# PROC099B_XDS110_Interface_1A.net
KiCad netlist of a schematic drawn in Altium Designer
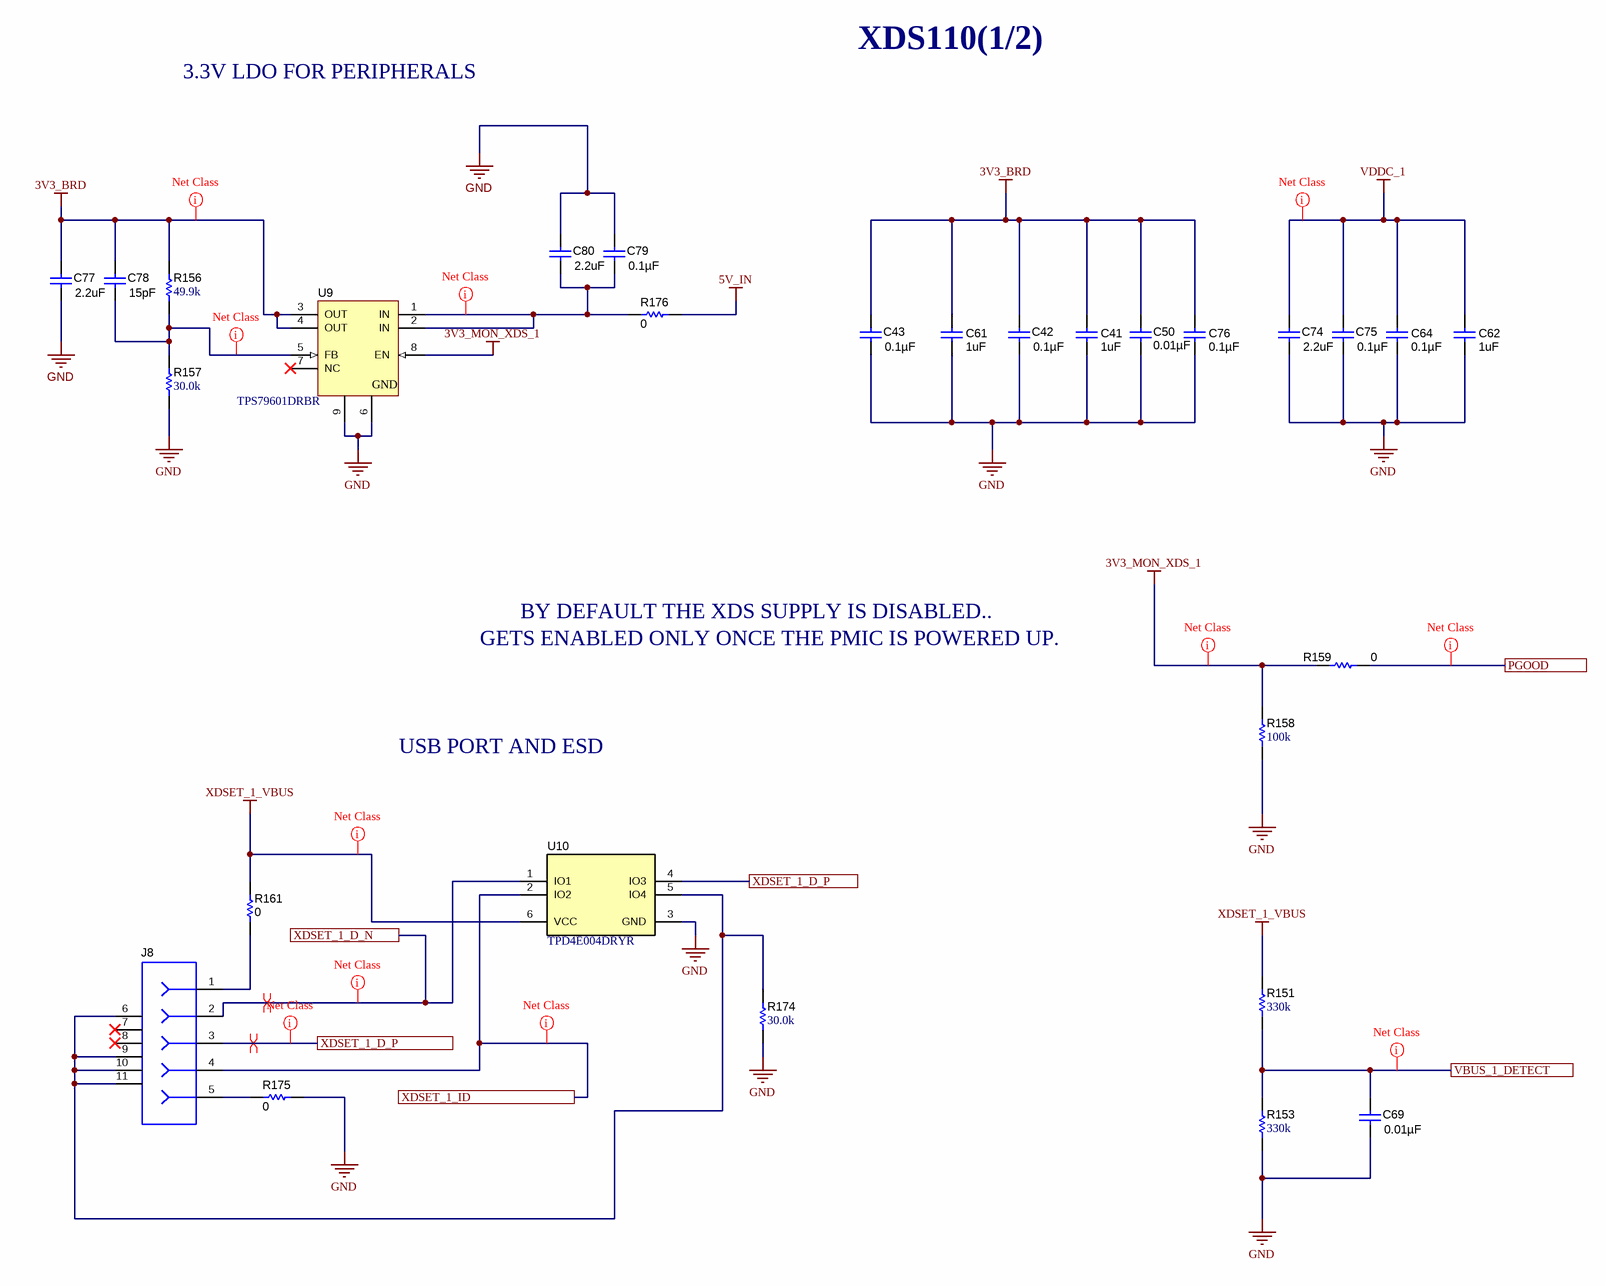
[diagram p0: PROC099B_XDS110 Interface_1A.SchDoc]

(export (version "E")
  (design (tool "Eeschema 10.0.6"))
  (components
    (comp (ref "C41")
      (value "GCM155C71A105KE38D")
      (footprint "0402_070")
      (description "CAP, CERM, 1 uF, 10 V, +/- 10%, X7S, AEC-Q200 Grade 1, 0402")
      (fields
        (field (name "MANUFACTURER") "MuRata")
        (field (name "VALUEDISPLAYED") "1uF")
        (field (name "PUBLISHER") "Texas Instruments")
      )
      (libsource (lib "Altium Vault - TI") (part "Capacitor"))
    )
    (comp (ref "C42")
      (value "C0402C104K8RACTU")
      (footprint "0402L")
      (description "CAP, CERM, 0.1 µF, 10 V,+/- 10%, X7R, 0402")
      (fields (field (name "MANUFACTURER") "Kemet") (field (name "VALUEDISPLAYED") "0.1µF"))
      (libsource (lib "Altium Vault - TI") (part "Capacitor"))
    )
    (comp (ref "C43")
      (value "C0402C104K8RACTU")
      (footprint "0402L")
      (description "CAP, CERM, 0.1 µF, 10 V,+/- 10%, X7R, 0402")
      (fields (field (name "MANUFACTURER") "Kemet") (field (name "VALUEDISPLAYED") "0.1µF"))
      (libsource (lib "Altium Vault - TI") (part "Capacitor"))
    )
    (comp (ref "C50")
      (value "C0402C103K4RACTU")
      (footprint "0402S")
      (description "CAP, CERM, 0.01 µF, 16 V,+/- 10%, X7R, 0402")
      (fields (field (name "MANUFACTURER") "Kemet") (field (name "VALUEDISPLAYED") "0.01µF"))
      (libsource (lib "Altium Vault - TI") (part "Capacitor"))
    )
    (comp (ref "C61")
      (value "GCM155C71A105KE38D")
      (footprint "0402_070")
      (description "CAP, CERM, 1 uF, 10 V, +/- 10%, X7S, AEC-Q200 Grade 1, 0402")
      (fields
        (field (name "MANUFACTURER") "MuRata")
        (field (name "VALUEDISPLAYED") "1uF")
        (field (name "PUBLISHER") "Texas Instruments")
      )
      (libsource (lib "Altium Vault - TI") (part "Capacitor"))
    )
    (comp (ref "C62")
      (value "GCM155C71A105KE38D")
      (footprint "0402_070")
      (description "CAP, CERM, 1 uF, 10 V, +/- 10%, X7S, AEC-Q200 Grade 1, 0402")
      (fields
        (field (name "MANUFACTURER") "MuRata")
        (field (name "VALUEDISPLAYED") "1uF")
        (field (name "PUBLISHER") "Texas Instruments")
      )
      (libsource (lib "Altium Vault - TI") (part "Capacitor"))
    )
    (comp (ref "C64")
      (value "C0402C104K8RACTU")
      (footprint "0402L")
      (description "CAP, CERM, 0.1 µF, 10 V,+/- 10%, X7R, 0402")
      (fields (field (name "MANUFACTURER") "Kemet") (field (name "VALUEDISPLAYED") "0.1µF"))
      (libsource (lib "Altium Vault - TI") (part "Capacitor"))
    )
    (comp (ref "C69")
      (value "C0402C103K4RACTU")
      (footprint "0402L")
      (description "CAP, CERM, 0.01 µF, 16 V,+/- 10%, X7R, 0402")
      (fields (field (name "MANUFACTURER") "Kemet") (field (name "VALUEDISPLAYED") "0.01µF"))
      (libsource (lib "Altium Vault - TI") (part "Capacitor"))
    )
    (comp (ref "C74")
      (value "C1005X7S1A225K050BC")
      (footprint "0402_065L")
      (description "CAP, CERM, 2.2 uF, 10 V, +/- 10%, X7S, 0402")
      (fields
        (field (name "MANUFACTURER") "TDK")
        (field (name "VALUEDISPLAYED") "2.2uF")
        (field (name "PUBLISHER") "Texas Instruments")
      )
      (libsource (lib "Altium Vault - TI") (part "CMP-0006302-2"))
    )
    (comp (ref "C75")
      (value "C0402C104K8RACTU")
      (footprint "0402L")
      (description "CAP, CERM, 0.1 µF, 10 V,+/- 10%, X7R, 0402")
      (fields (field (name "MANUFACTURER") "Kemet") (field (name "VALUEDISPLAYED") "0.1µF"))
      (libsource (lib "Altium Vault - TI") (part "Capacitor"))
    )
    (comp (ref "C76")
      (value "C0402C104K8RACTU")
      (footprint "0402L")
      (description "CAP, CERM, 0.1 µF, 10 V,+/- 10%, X7R, 0402")
      (fields (field (name "MANUFACTURER") "Kemet") (field (name "VALUEDISPLAYED") "0.1µF"))
      (libsource (lib "Altium Vault - TI") (part "Capacitor"))
    )
    (comp (ref "C77")
      (value "C1005X7S1A225K050BC")
      (footprint "0402_065L")
      (description "CAP, CERM, 2.2 uF, 10 V, +/- 10%, X7S, 0402")
      (fields
        (field (name "MANUFACTURER") "TDK")
        (field (name "VALUEDISPLAYED") "2.2uF")
        (field (name "PUBLISHER") "Texas Instruments")
      )
      (libsource (lib "Altium Vault - TI") (part "CMP-0006302-2"))
    )
    (comp (ref "C78")
      (value "04025A150FAT2A")
      (footprint "0402L")
      (description "CAP, CERM, 15 pF, 50 V,+/- 1%, C0G/NP0, 0402")
      (fields (field (name "MANUFACTURER") "AVX") (field (name "VALUEDISPLAYED") "15pF"))
      (libsource (lib "Altium Vault - TI") (part "Capacitor"))
    )
    (comp (ref "C79")
      (value "C0402C104K8RACTU")
      (footprint "0402L")
      (description "CAP, CERM, 0.1 µF, 10 V,+/- 10%, X7R, 0402")
      (fields (field (name "MANUFACTURER") "Kemet") (field (name "VALUEDISPLAYED") "0.1µF"))
      (libsource (lib "Altium Vault - TI") (part "Capacitor"))
    )
    (comp (ref "C80")
      (value "C1005X7S1A225K050BC")
      (footprint "0402_065L")
      (description "CAP, CERM, 2.2 uF, 10 V, +/- 10%, X7S, 0402")
      (fields
        (field (name "MANUFACTURER") "TDK")
        (field (name "VALUEDISPLAYED") "2.2uF")
        (field (name "PUBLISHER") "Texas Instruments")
      )
      (libsource (lib "Altium Vault - TI") (part "CMP-0006302-2"))
    )
    (comp (ref "J8")
      (value "105017-0001")
      (footprint "CONN_105017-0001")
      (description "Connector, Receptacle, Micro-USB Type B, R/A, Bottom Mount SMT")
      (fields (field (name "MANUFACTURER") "Molex") (field (name "PUBLISHER") "Texas Instruments"))
      (libsource (lib "Altium Vault - TI") (part "CONN_105017-0001"))
    )
    (comp (ref "R151")
      (value "CRCW0402330KFKED")
      (footprint "0402L")
      (description "RES, 330 k, 1%, 0.063 W, AEC-Q200 Grade 0, 0402")
      (fields (field (name "MANUFACTURER") "Vishay-Dale") (field (name "VALUEDISPLAYED") "330k"))
      (libsource (lib "Altium Vault - TI") (part "Resistor"))
    )
    (comp (ref "R153")
      (value "CRCW0402330KFKED")
      (footprint "0402L")
      (description "RES, 330 k, 1%, 0.063 W, AEC-Q200 Grade 0, 0402")
      (fields (field (name "MANUFACTURER") "Vishay-Dale") (field (name "VALUEDISPLAYED") "330k"))
      (libsource (lib "Altium Vault - TI") (part "Resistor"))
    )
    (comp (ref "R156")
      (value "CRCW040249K9FKED")
      (footprint "0402L")
      (description "RES, 49.9 k, 1%, 0.063 W, AEC-Q200 Grade 0, 0402")
      (fields (field (name "MANUFACTURER") "Vishay-Dale") (field (name "VALUEDISPLAYED") "49.9k"))
      (libsource (lib "Altium Vault - TI") (part "Resistor"))
    )
    (comp (ref "R157")
      (value "CRCW040230K0FKED")
      (footprint "0402L")
      (description "RES, 30.0 k, 1%, 0.063 W, AEC-Q200 Grade 0, 0402")
      (fields (field (name "MANUFACTURER") "Vishay-Dale") (field (name "VALUEDISPLAYED") "30.0k"))
      (libsource (lib "Altium Vault - TI") (part "Resistor"))
    )
    (comp (ref "R158")
      (value "CRCW0402100KFKED")
      (footprint "0402L")
      (description "RES, 100 k, 1%, 0.063 W, AEC-Q200 Grade 0, 0402")
      (fields (field (name "MANUFACTURER") "Vishay-Dale") (field (name "VALUEDISPLAYED") "100k"))
      (libsource (lib "Altium Vault - TI") (part "Resistor"))
    )
    (comp (ref "R159")
      (value "ERJ-2GE0R00X")
      (footprint "0402L")
      (description "RES, 0, 5%, 0.063 W, 0402")
      (fields
        (field (name "MANUFACTURER") "Panasonic")
        (field (name "VALUEDISPLAYED") "0")
        (field (name "PUBLISHER") "Texas Instruments")
      )
      (libsource (lib "Altium Vault - TI") (part "Resistor"))
    )
    (comp (ref "R161")
      (value "MCT06030Z0000ZP500")
      (footprint "0603")
      (description "RES, 0, 5%, 0.125 W, 0603")
      (fields
        (field (name "MANUFACTURER") "Vishay/Beyschlag")
        (field (name "VALUEDISPLAYED") "0")
        (field (name "PUBLISHER") "Texas Instruments")
      )
      (libsource (lib "Altium Vault - TI") (part "Resistor"))
    )
    (comp (ref "R174")
      (value "CRCW040230K0FKED")
      (footprint "0402L")
      (description "RES, 30.0 k, 1%, 0.063 W, AEC-Q200 Grade 0, 0402")
      (fields (field (name "MANUFACTURER") "Vishay-Dale") (field (name "VALUEDISPLAYED") "30.0k"))
      (libsource (lib "Altium Vault - TI") (part "Resistor"))
    )
    (comp (ref "R175")
      (value "MCT06030Z0000ZP500")
      (footprint "0603")
      (description "RES, 0, 5%, 0.125 W, 0603")
      (fields
        (field (name "MANUFACTURER") "Vishay/Beyschlag")
        (field (name "VALUEDISPLAYED") "0")
        (field (name "PUBLISHER") "Texas Instruments")
      )
      (libsource (lib "Altium Vault - TI") (part "Resistor"))
    )
    (comp (ref "R176")
      (value "MCT06030Z0000ZP500")
      (footprint "0603")
      (description "RES, 0, 5%, 0.125 W, 0603")
      (fields
        (field (name "MANUFACTURER") "Vishay/Beyschlag")
        (field (name "VALUEDISPLAYED") "0")
        (field (name "PUBLISHER") "Texas Instruments")
      )
      (libsource (lib "Altium Vault - TI") (part "Resistor"))
    )
    (comp (ref "U9")
      (value "TPS79601DRBR")
      (footprint "DRB0008B")
      (fields (field (name "MANUFACTURER") "Texas Instruments") (field (name "PARTNUMBER") "TPS79601DRBR"))
      (libsource (lib "Altium Vault - TI") (part "CMP-0036402-3"))
    )
    (comp (ref "U10")
      (value "TPD4E004DRYR")
      (footprint "DRY0006A")
      (fields (field (name "MANUFACTURER") "Texas Instruments") (field (name "PARTNUMBER") "TPD4E004DRYR"))
      (libsource (lib "Altium Vault - TI") (part "CMP-0043115-2"))
    )
  )
  (nets
    (net (code "1") (name "/PGOOD") (class "Default")
      (node (ref "R159") (pin "1") (pinfunction "1_1") (pintype "passive"))
    )
    (net (code "2") (name "/VBUS_1_DETECT") (class "Default")
      (node (ref "C69") (pin "2") (pinfunction "2_2") (pintype "passive"))
      (node (ref "R151") (pin "1") (pinfunction "1_1") (pintype "passive"))
      (node (ref "R153") (pin "2") (pinfunction "2_2") (pintype "passive"))
    )
    (net (code "3") (name "/XDSET_1_D_N") (class "Default")
      (node (ref "J8") (pin "2") (pintype "passive"))
      (node (ref "U10") (pin "1") (pinfunction "IO1_1") (pintype "passive"))
    )
    (net (code "4") (name "/XDSET_1_D_P") (class "Default")
      (node (ref "J8") (pin "3") (pintype "passive"))
      (node (ref "U10") (pin "4") (pinfunction "IO3_4") (pintype "passive"))
    )
    (net (code "5") (name "/XDSET_1_ID") (class "Default")
      (node (ref "J8") (pin "4") (pintype "passive"))
      (node (ref "U10") (pin "2") (pinfunction "IO2_2") (pintype "passive"))
    )
    (net (code "6") (name "3V3_BRD") (class "Default")
      (node (ref "C41") (pin "1") (pinfunction "1_1") (pintype "passive"))
      (node (ref "C42") (pin "2") (pinfunction "2_2") (pintype "passive"))
      (node (ref "C43") (pin "2") (pinfunction "2_2") (pintype "passive"))
      (node (ref "C50") (pin "1") (pinfunction "1_1") (pintype "passive"))
      (node (ref "C61") (pin "1") (pinfunction "1_1") (pintype "passive"))
      (node (ref "C76") (pin "2") (pinfunction "2_2") (pintype "passive"))
      (node (ref "C77") (pin "2") (pinfunction "2_2") (pintype "passive"))
      (node (ref "C78") (pin "2") (pinfunction "2_2") (pintype "passive"))
      (node (ref "R156") (pin "2") (pinfunction "2_2") (pintype "passive"))
      (node (ref "U9") (pin "3") (pinfunction "OUT_3") (pintype "power_in"))
      (node (ref "U9") (pin "4") (pinfunction "OUT_4") (pintype "power_in"))
    )
    (net (code "7") (name "3V3_MON_XDS_1") (class "Default")
      (node (ref "R158") (pin "2") (pinfunction "2_2") (pintype "passive"))
      (node (ref "R159") (pin "2") (pinfunction "2_2") (pintype "passive"))
      (node (ref "U9") (pin "8") (pinfunction "EN_8") (pintype "input"))
    )
    (net (code "8") (name "5V_IN") (class "Default")
      (node (ref "R176") (pin "2") (pinfunction "2_2") (pintype "passive"))
    )
    (net (code "9") (name "GND") (class "Default")
      (node (ref "C41") (pin "2") (pinfunction "2_2") (pintype "passive"))
      (node (ref "C42") (pin "1") (pinfunction "1_1") (pintype "passive"))
      (node (ref "C43") (pin "1") (pinfunction "1_1") (pintype "passive"))
      (node (ref "C50") (pin "2") (pinfunction "2_2") (pintype "passive"))
      (node (ref "C61") (pin "2") (pinfunction "2_2") (pintype "passive"))
      (node (ref "C62") (pin "2") (pinfunction "2_2") (pintype "passive"))
      (node (ref "C64") (pin "1") (pinfunction "1_1") (pintype "passive"))
      (node (ref "C69") (pin "1") (pinfunction "1_1") (pintype "passive"))
      (node (ref "C74") (pin "1") (pinfunction "1_1") (pintype "passive"))
      (node (ref "C75") (pin "1") (pinfunction "1_1") (pintype "passive"))
      (node (ref "C76") (pin "1") (pinfunction "1_1") (pintype "passive"))
      (node (ref "C77") (pin "1") (pinfunction "1_1") (pintype "passive"))
      (node (ref "C79") (pin "1") (pinfunction "1_1") (pintype "passive"))
      (node (ref "C80") (pin "1") (pinfunction "1_1") (pintype "passive"))
      (node (ref "R153") (pin "1") (pinfunction "1_1") (pintype "passive"))
      (node (ref "R157") (pin "1") (pinfunction "1_1") (pintype "passive"))
      (node (ref "R158") (pin "1") (pinfunction "1_1") (pintype "passive"))
      (node (ref "R174") (pin "1") (pinfunction "1_1") (pintype "passive"))
      (node (ref "R175") (pin "1") (pinfunction "1_1") (pintype "passive"))
      (node (ref "U10") (pin "3") (pinfunction "GND_3") (pintype "power_in"))
      (node (ref "U9") (pin "6") (pinfunction "GND_6") (pintype "power_in"))
      (node (ref "U9") (pin "9") (pinfunction "GND_9") (pintype "power_in"))
    )
    (net (code "10") (name "Net-(C79-Pad2)") (class "Default")
      (node (ref "C79") (pin "2") (pinfunction "2_2") (pintype "passive"))
      (node (ref "C80") (pin "2") (pinfunction "2_2") (pintype "passive"))
      (node (ref "R176") (pin "1") (pinfunction "1_1") (pintype "passive"))
      (node (ref "U9") (pin "1") (pinfunction "IN_1") (pintype "power_in"))
      (node (ref "U9") (pin "2") (pinfunction "IN_2") (pintype "power_in"))
    )
    (net (code "11") (name "Net-(J8-Pad1)") (class "Default")
      (node (ref "J8") (pin "1") (pintype "passive"))
      (node (ref "R161") (pin "1") (pinfunction "1_1") (pintype "passive"))
    )
    (net (code "12") (name "Net-(J8-Pad5)") (class "Default")
      (node (ref "J8") (pin "5") (pintype "passive"))
      (node (ref "R175") (pin "2") (pinfunction "2_2") (pintype "passive"))
    )
    (net (code "13") (name "Net-(U9-FB)") (class "Default")
      (node (ref "C78") (pin "1") (pinfunction "1_1") (pintype "passive"))
      (node (ref "R156") (pin "1") (pinfunction "1_1") (pintype "passive"))
      (node (ref "R157") (pin "2") (pinfunction "2_2") (pintype "passive"))
      (node (ref "U9") (pin "5") (pinfunction "FB_5") (pintype "input"))
    )
    (net (code "14") (name "Net-(U10-IO4)") (class "Default")
      (node (ref "J8") (pin "10") (pintype "passive"))
      (node (ref "J8") (pin "11") (pintype "passive"))
      (node (ref "J8") (pin "6") (pintype "passive"))
      (node (ref "J8") (pin "9") (pintype "passive"))
      (node (ref "R174") (pin "2") (pinfunction "2_2") (pintype "passive"))
      (node (ref "U10") (pin "5") (pinfunction "IO4_5") (pintype "passive"))
    )
    (net (code "15") (name "VDDC_1") (class "Default")
      (node (ref "C62") (pin "1") (pinfunction "1_1") (pintype "passive"))
      (node (ref "C64") (pin "2") (pinfunction "2_2") (pintype "passive"))
      (node (ref "C74") (pin "2") (pinfunction "2_2") (pintype "passive"))
      (node (ref "C75") (pin "2") (pinfunction "2_2") (pintype "passive"))
    )
    (net (code "16") (name "XDSET_1_VBUS") (class "Default")
      (node (ref "R151") (pin "2") (pinfunction "2_2") (pintype "passive"))
      (node (ref "R161") (pin "2") (pinfunction "2_2") (pintype "passive"))
      (node (ref "U10") (pin "6") (pinfunction "VCC_6") (pintype "power_in"))
    )
    (net (code "17") (name "unconnected-(J8-Pad7)") (class "Default")
      (node (ref "J8") (pin "7") (pintype "passive+no_connect"))
    )
    (net (code "18") (name "unconnected-(J8-Pad8)") (class "Default")
      (node (ref "J8") (pin "8") (pintype "passive+no_connect"))
    )
    (net (code "19") (name "unconnected-(U9-NC-Pad7)") (class "Default")
      (node (ref "U9") (pin "7") (pinfunction "NC_7") (pintype "passive+no_connect"))
    )
  )
)
